# 5vdcdc_2_0.net
KiCad netlist of a schematic drawn in EAGLE
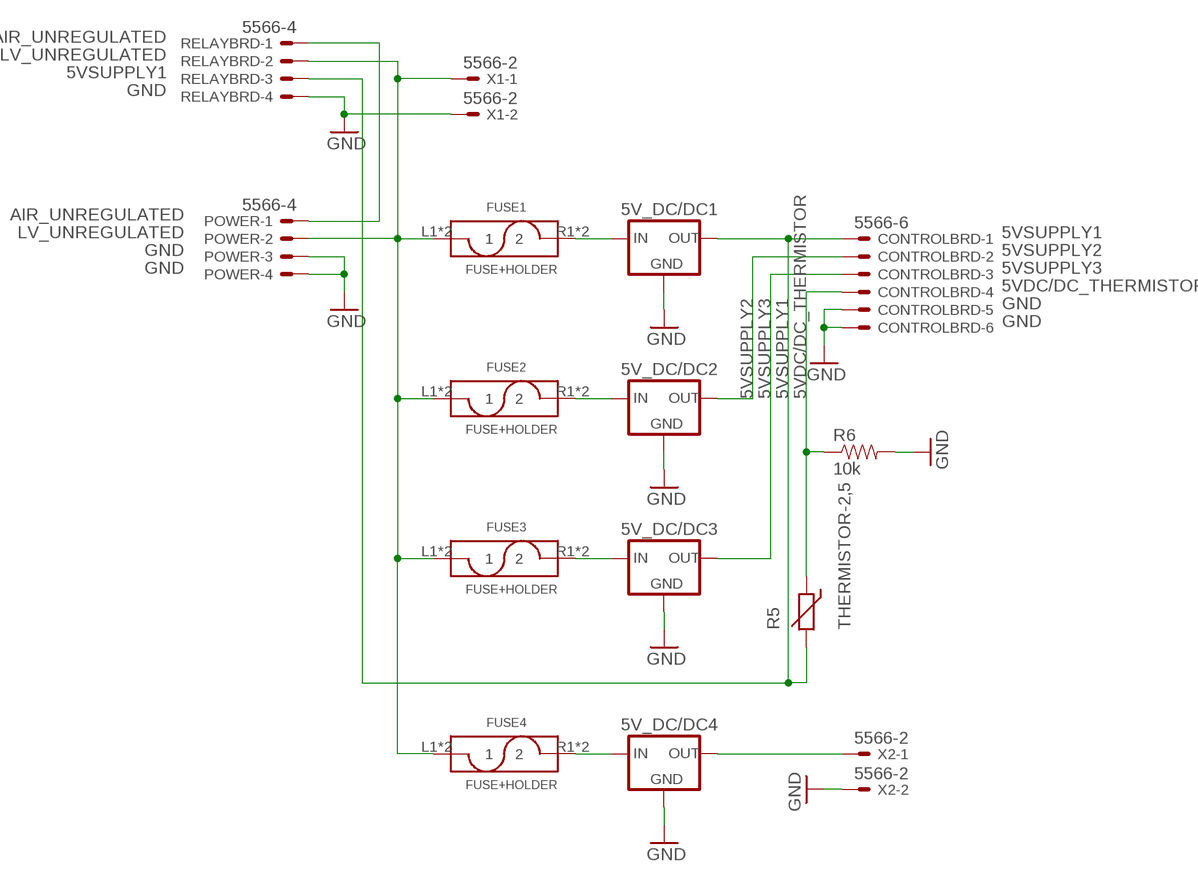
[diagram p0: schematic, sheet 1]

(export (version "E")
  (design (tool "Eeschema 10.0.6"))
  (components
    (comp (ref "5V_DC/DC1")
      (value "5V_REGULATORLINEAR")
      (footprint "eagle-import:TO-220-SINK")
      (libsource (lib "eagle-import") (part "5V_REGULATORLINEAR"))
    )
    (comp (ref "5V_DC/DC2")
      (value "5V_REGULATORLINEAR")
      (footprint "eagle-import:TO-220-SINK")
      (libsource (lib "eagle-import") (part "5V_REGULATORLINEAR"))
    )
    (comp (ref "5V_DC/DC3")
      (value "5V_REGULATORLINEAR")
      (footprint "eagle-import:TO-220-SINK")
      (libsource (lib "eagle-import") (part "5V_REGULATORLINEAR"))
    )
    (comp (ref "5V_DC/DC4")
      (value "5V_REGULATORLINEAR")
      (footprint "eagle-import:TO-220-SINK")
      (libsource (lib "eagle-import") (part "5V_REGULATORLINEAR"))
    )
    (comp (ref "CONTROLBRD")
      (value "5566-6")
      (footprint "eagle-import:5566-6")
      (fields (field (name "MPN") "95566-61002"))
      (libsource (lib "eagle-import") (part "5566-6"))
    )
    (comp (ref "FUSE1")
      (value "FUSE+HOLDER")
      (footprint "eagle-import:FUSE-HOLDER")
      (libsource (lib "eagle-import") (part "FUSE+HOLDER"))
    )
    (comp (ref "FUSE2")
      (value "FUSE+HOLDER")
      (footprint "eagle-import:FUSE-HOLDER")
      (libsource (lib "eagle-import") (part "FUSE+HOLDER"))
    )
    (comp (ref "FUSE3")
      (value "FUSE+HOLDER")
      (footprint "eagle-import:FUSE-HOLDER")
      (libsource (lib "eagle-import") (part "FUSE+HOLDER"))
    )
    (comp (ref "FUSE4")
      (value "FUSE+HOLDER")
      (footprint "eagle-import:FUSE-HOLDER")
      (libsource (lib "eagle-import") (part "FUSE+HOLDER"))
    )
    (comp (ref "POWER")
      (value "5566-4")
      (footprint "eagle-import:5566-4")
      (libsource (lib "eagle-import") (part "5566-4"))
    )
    (comp (ref "R5")
      (value "THERMISTOR-2,5")
      (footprint "eagle-import:RS-2,5")
      (libsource (lib "eagle-import") (part "THERMISTOR-2,5"))
    )
    (comp (ref "R6")
      (value "10k")
      (footprint "eagle-import:AXIAL-0.3")
      (libsource (lib "eagle-import") (part "RESISTORAXIAL-0.3"))
    )
    (comp (ref "RELAYBRD")
      (value "5566-4")
      (footprint "eagle-import:5566-4")
      (libsource (lib "eagle-import") (part "5566-4"))
    )
    (comp (ref "X1")
      (value "5566-2")
      (footprint "eagle-import:5566-2")
      (libsource (lib "eagle-import") (part "5566-2"))
    )
    (comp (ref "X2")
      (value "5566-2")
      (footprint "eagle-import:5566-2")
      (libsource (lib "eagle-import") (part "5566-2"))
    )
  )
  (nets
    (net (code "1") (name "/5VDC{slash}DC_THERMISTOR") (class "Default")
      (node (ref "CONTROLBRD") (pin "4") (pinfunction "S_4") (pintype "passive"))
      (node (ref "R5") (pin "1") (pinfunction "1_1") (pintype "passive"))
      (node (ref "R6") (pin "P$1") (pinfunction "1_P$1") (pintype "passive"))
    )
    (net (code "2") (name "/5VSUPPLY1") (class "Default")
      (node (ref "5V_DC/DC1") (pin "3") (pinfunction "OUT_3") (pintype "output"))
      (node (ref "CONTROLBRD") (pin "1") (pinfunction "S_1") (pintype "passive"))
      (node (ref "R5") (pin "2") (pinfunction "2_2") (pintype "passive"))
      (node (ref "RELAYBRD") (pin "3") (pinfunction "S_3") (pintype "passive"))
    )
    (net (code "3") (name "/5VSUPPLY2") (class "Default")
      (node (ref "5V_DC/DC2") (pin "3") (pinfunction "OUT_3") (pintype "output"))
      (node (ref "CONTROLBRD") (pin "2") (pinfunction "S_2") (pintype "passive"))
    )
    (net (code "4") (name "/5VSUPPLY3") (class "Default")
      (node (ref "5V_DC/DC3") (pin "3") (pinfunction "OUT_3") (pintype "output"))
      (node (ref "CONTROLBRD") (pin "3") (pinfunction "S_3") (pintype "passive"))
    )
    (net (code "5") (name "/AIR_UNREGULATED") (class "Default")
      (node (ref "POWER") (pin "1") (pinfunction "S_1") (pintype "passive"))
      (node (ref "RELAYBRD") (pin "1") (pinfunction "S_1") (pintype "passive"))
    )
    (net (code "6") (name "/LV_UNREGULATED") (class "Default")
      (node (ref "FUSE1") (pin "L1") (pinfunction "1_L1") (pintype "bidirectional"))
      (node (ref "FUSE1") (pin "L2") (pinfunction "1_L2") (pintype "bidirectional"))
      (node (ref "FUSE2") (pin "L1") (pinfunction "1_L1") (pintype "bidirectional"))
      (node (ref "FUSE2") (pin "L2") (pinfunction "1_L2") (pintype "bidirectional"))
      (node (ref "FUSE3") (pin "L1") (pinfunction "1_L1") (pintype "bidirectional"))
      (node (ref "FUSE3") (pin "L2") (pinfunction "1_L2") (pintype "bidirectional"))
      (node (ref "FUSE4") (pin "L1") (pinfunction "1_L1") (pintype "bidirectional"))
      (node (ref "FUSE4") (pin "L2") (pinfunction "1_L2") (pintype "bidirectional"))
      (node (ref "POWER") (pin "2") (pinfunction "S_2") (pintype "passive"))
      (node (ref "RELAYBRD") (pin "2") (pinfunction "S_2") (pintype "passive"))
      (node (ref "X1") (pin "1") (pinfunction "S_1") (pintype "passive"))
    )
    (net (code "7") (name "GND") (class "Default")
      (node (ref "5V_DC/DC1") (pin "2") (pinfunction "GND_2") (pintype "input"))
      (node (ref "5V_DC/DC2") (pin "2") (pinfunction "GND_2") (pintype "input"))
      (node (ref "5V_DC/DC3") (pin "2") (pinfunction "GND_2") (pintype "input"))
      (node (ref "5V_DC/DC4") (pin "2") (pinfunction "GND_2") (pintype "input"))
      (node (ref "CONTROLBRD") (pin "5") (pinfunction "S_5") (pintype "passive"))
      (node (ref "CONTROLBRD") (pin "6") (pinfunction "S_6") (pintype "passive"))
      (node (ref "POWER") (pin "3") (pinfunction "S_3") (pintype "passive"))
      (node (ref "POWER") (pin "4") (pinfunction "S_4") (pintype "passive"))
      (node (ref "R6") (pin "P$2") (pinfunction "2_P$2") (pintype "passive"))
      (node (ref "RELAYBRD") (pin "4") (pinfunction "S_4") (pintype "passive"))
      (node (ref "X1") (pin "2") (pinfunction "S_2") (pintype "passive"))
      (node (ref "X2") (pin "2") (pinfunction "S_2") (pintype "passive"))
    )
    (net (code "8") (name "Net-(5V_DC/DC1-IN)") (class "Default")
      (node (ref "5V_DC/DC1") (pin "1") (pinfunction "IN_1") (pintype "input"))
      (node (ref "FUSE1") (pin "R1") (pinfunction "2_R1") (pintype "bidirectional"))
      (node (ref "FUSE1") (pin "R2") (pinfunction "2_R2") (pintype "bidirectional"))
    )
    (net (code "9") (name "Net-(5V_DC/DC2-IN)") (class "Default")
      (node (ref "5V_DC/DC2") (pin "1") (pinfunction "IN_1") (pintype "input"))
      (node (ref "FUSE2") (pin "R1") (pinfunction "2_R1") (pintype "bidirectional"))
      (node (ref "FUSE2") (pin "R2") (pinfunction "2_R2") (pintype "bidirectional"))
    )
    (net (code "10") (name "Net-(5V_DC/DC3-IN)") (class "Default")
      (node (ref "5V_DC/DC3") (pin "1") (pinfunction "IN_1") (pintype "input"))
      (node (ref "FUSE3") (pin "R1") (pinfunction "2_R1") (pintype "bidirectional"))
      (node (ref "FUSE3") (pin "R2") (pinfunction "2_R2") (pintype "bidirectional"))
    )
    (net (code "11") (name "Net-(5V_DC/DC4-IN)") (class "Default")
      (node (ref "5V_DC/DC4") (pin "1") (pinfunction "IN_1") (pintype "input"))
      (node (ref "FUSE4") (pin "R1") (pinfunction "2_R1") (pintype "bidirectional"))
      (node (ref "FUSE4") (pin "R2") (pinfunction "2_R2") (pintype "bidirectional"))
    )
    (net (code "12") (name "Net-(5V_DC/DC4-OUT)") (class "Default")
      (node (ref "5V_DC/DC4") (pin "3") (pinfunction "OUT_3") (pintype "output"))
      (node (ref "X2") (pin "1") (pinfunction "S_1") (pintype "passive"))
    )
  )
)
